# heart.net
KiCad netlist of a schematic drawn in EAGLE
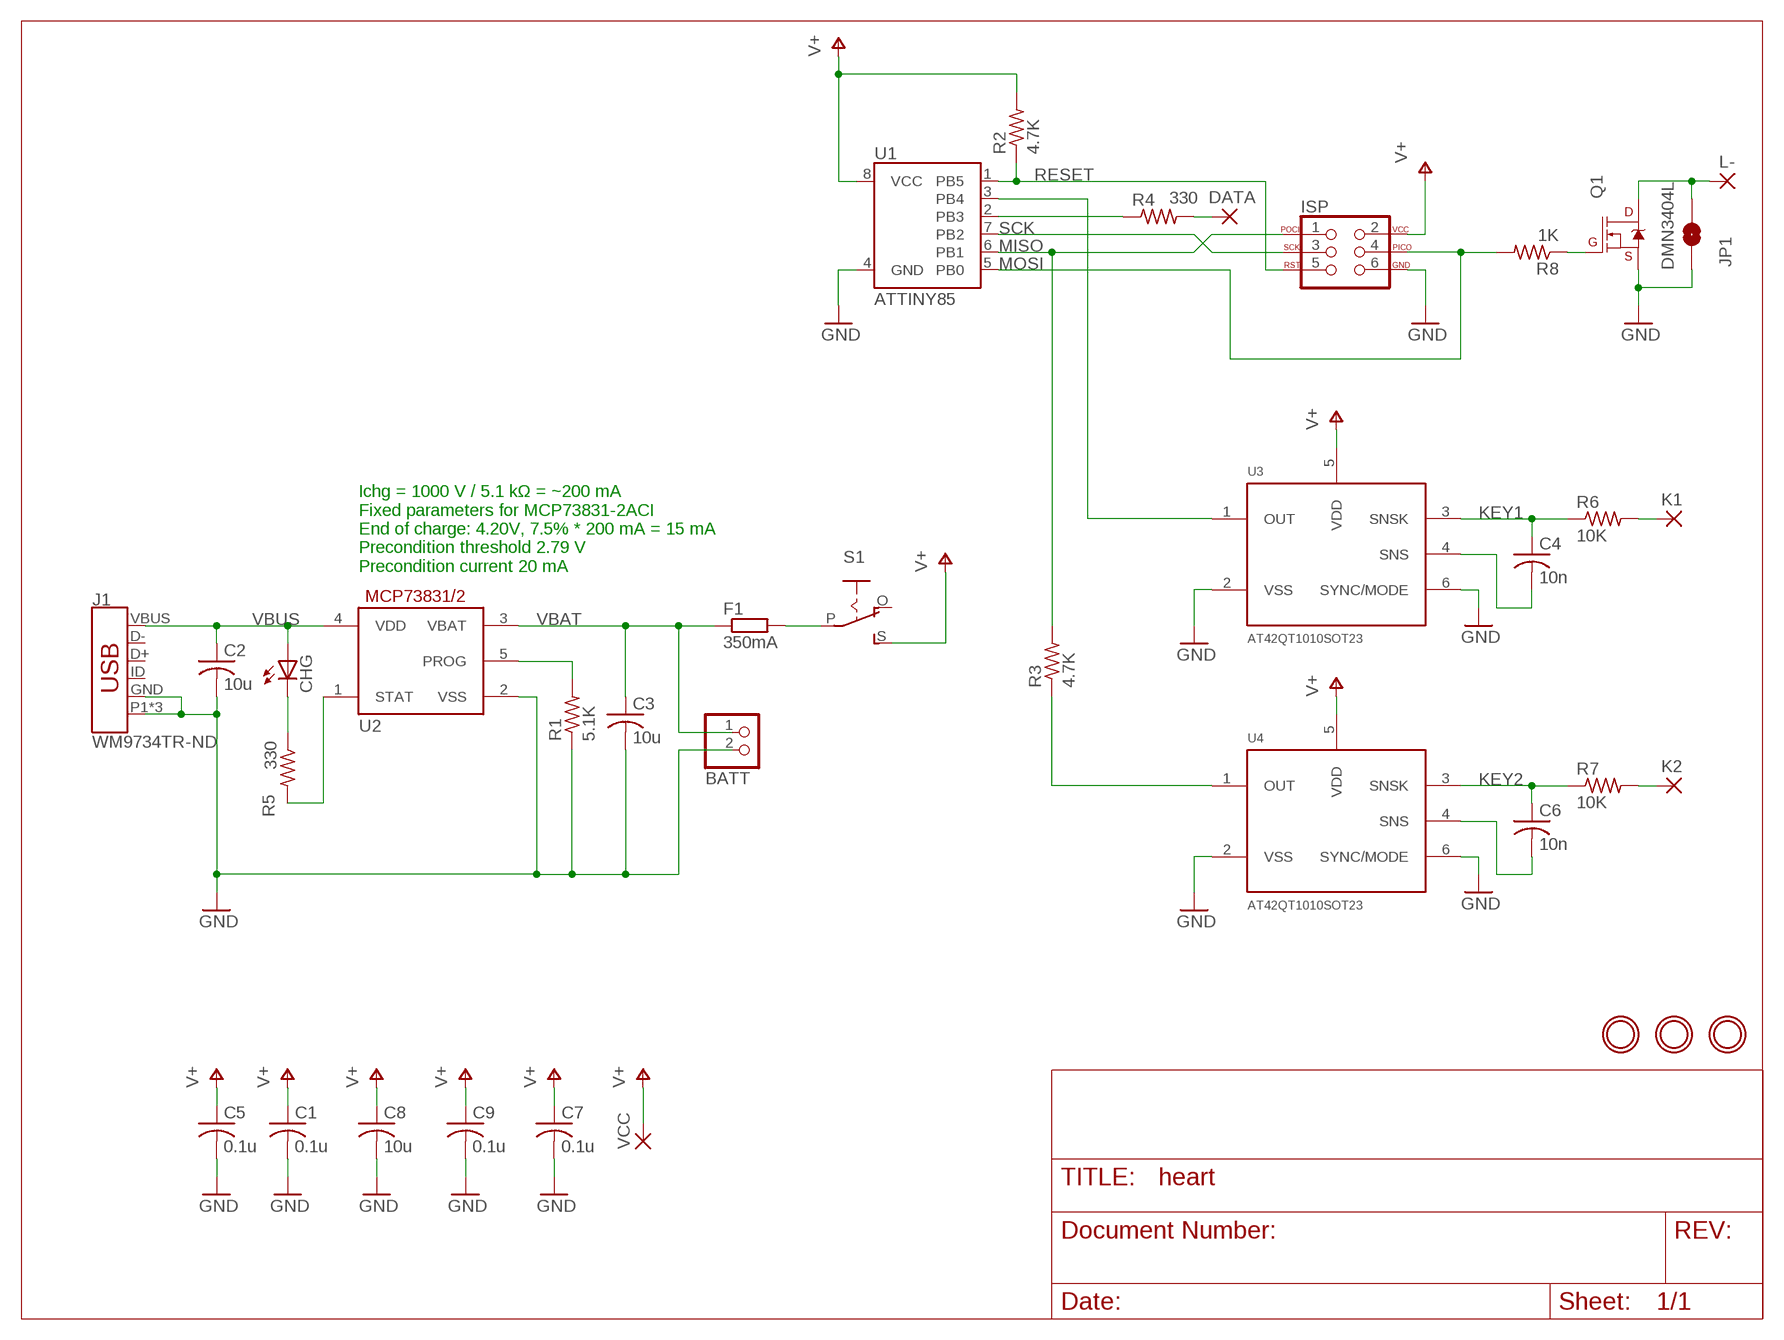
[diagram p0: schematic, sheet 1]

(export (version "E")
  (design (tool "Eeschema 10.0.6"))
  (components
    (comp (ref "BATT")
      (value "JST_2PIN-THM-RA")
      (footprint "eagle-import:JST-PH-2-THM-RA")
      (libsource (lib "eagle-import") (part "JST_2PIN-THM-RA"))
    )
    (comp (ref "C1")
      (value "0.1u")
      (footprint "eagle-import:C0603")
      (libsource (lib "eagle-import") (part "C-USC0603"))
    )
    (comp (ref "C2")
      (value "10u")
      (footprint "eagle-import:C0603")
      (libsource (lib "eagle-import") (part "C-USC0603"))
    )
    (comp (ref "C3")
      (value "10u")
      (footprint "eagle-import:C0603")
      (libsource (lib "eagle-import") (part "C-USC0603"))
    )
    (comp (ref "C4")
      (value "10n")
      (footprint "eagle-import:C0603")
      (libsource (lib "eagle-import") (part "C-USC0603"))
    )
    (comp (ref "C5")
      (value "0.1u")
      (footprint "eagle-import:C0603")
      (libsource (lib "eagle-import") (part "C-USC0603"))
    )
    (comp (ref "C6")
      (value "10n")
      (footprint "eagle-import:C0603")
      (libsource (lib "eagle-import") (part "C-USC0603"))
    )
    (comp (ref "C7")
      (value "0.1u")
      (footprint "eagle-import:C0603")
      (libsource (lib "eagle-import") (part "C-USC0603"))
    )
    (comp (ref "C8")
      (value "10u")
      (footprint "eagle-import:C0603")
      (libsource (lib "eagle-import") (part "C-USC0603"))
    )
    (comp (ref "C9")
      (value "0.1u")
      (footprint "eagle-import:C0603")
      (libsource (lib "eagle-import") (part "C-USC0603"))
    )
    (comp (ref "CHG")
      (value "LEDCHIP-LED0805")
      (footprint "eagle-import:CHIP-LED0805")
      (libsource (lib "eagle-import") (part "LEDCHIP-LED0805"))
    )
    (comp (ref "DATA")
      (value "2,15/1,0")
      (footprint "eagle-import:2,15_1,0")
      (libsource (lib "eagle-import") (part "2,15/1,0"))
    )
    (comp (ref "F1")
      (value "350mA")
      (footprint "eagle-import:R0603")
      (libsource (lib "eagle-import") (part "R-EU_R0603"))
    )
    (comp (ref "ISP")
      (value "AVR_SPI_PROG_3X2PTH")
      (footprint "eagle-import:2X3")
      (libsource (lib "eagle-import") (part "AVR_SPI_PROG_3X2PTH"))
    )
    (comp (ref "J1")
      (value "WM9734TR-ND")
      (footprint "eagle-import:USB-B-MICRO-SMD_VERT")
      (libsource (lib "eagle-import") (part "USB_MICRO-B_FEMALE-SMT-VERT"))
    )
    (comp (ref "JP1")
      (value "JUMPER-SMT_2_NO_NO-SILK")
      (footprint "eagle-import:SMT-JUMPER_2_NO_NO-SILK")
      (libsource (lib "eagle-import") (part "JUMPER-SMT_2_NO_NO-SILK"))
    )
    (comp (ref "K1")
      (value "2,15/1,0")
      (footprint "eagle-import:2,15_1,0")
      (libsource (lib "eagle-import") (part "2,15/1,0"))
    )
    (comp (ref "K2")
      (value "2,15/1,0")
      (footprint "eagle-import:2,15_1,0")
      (libsource (lib "eagle-import") (part "2,15/1,0"))
    )
    (comp (ref "L-")
      (value "2,15/1,0")
      (footprint "eagle-import:2,15_1,0")
      (libsource (lib "eagle-import") (part "2,15/1,0"))
    )
    (comp (ref "Q1")
      (value "DMN3404L")
      (footprint "eagle-import:SOT23-3")
      (libsource (lib "eagle-import") (part "MOSFET-NCH-AO3404A"))
    )
    (comp (ref "R1")
      (value "5.1K")
      (footprint "eagle-import:R0603")
      (libsource (lib "eagle-import") (part "R-US_R0603"))
    )
    (comp (ref "R2")
      (value "4.7K")
      (footprint "eagle-import:R0603")
      (libsource (lib "eagle-import") (part "R-US_R0603"))
    )
    (comp (ref "R3")
      (value "4.7K")
      (footprint "eagle-import:R0603")
      (libsource (lib "eagle-import") (part "R-US_R0603"))
    )
    (comp (ref "R4")
      (value "330")
      (footprint "eagle-import:R0603")
      (libsource (lib "eagle-import") (part "R-US_R0603"))
    )
    (comp (ref "R5")
      (value "330")
      (footprint "eagle-import:R0603")
      (libsource (lib "eagle-import") (part "R-US_R0603"))
    )
    (comp (ref "R6")
      (value "10K")
      (footprint "eagle-import:R0603")
      (libsource (lib "eagle-import") (part "R-US_R0603"))
    )
    (comp (ref "R7")
      (value "10K")
      (footprint "eagle-import:R0603")
      (libsource (lib "eagle-import") (part "R-US_R0603"))
    )
    (comp (ref "R8")
      (value "1K")
      (footprint "eagle-import:R0603")
      (libsource (lib "eagle-import") (part "R-US_R0603"))
    )
    (comp (ref "S1")
      (value "EG1218S")
      (footprint "eagle-import:EG1218")
      (libsource (lib "eagle-import") (part "EG1218S"))
    )
    (comp (ref "U$1")
      (value "MICROBUILDER_MOUNTINGHOLE2.0")
      (footprint "eagle-import:MICROBUILDER_MOUNTINGHOLE_2.0_PLATED")
      (libsource (lib "eagle-import") (part "MICROBUILDER_MOUNTINGHOLE2.0"))
    )
    (comp (ref "U$2")
      (value "MICROBUILDER_MOUNTINGHOLE2.0")
      (footprint "eagle-import:MICROBUILDER_MOUNTINGHOLE_2.0_PLATED")
      (libsource (lib "eagle-import") (part "MICROBUILDER_MOUNTINGHOLE2.0"))
    )
    (comp (ref "U$4")
      (value "MICROBUILDER_MOUNTINGHOLE2.0")
      (footprint "eagle-import:MICROBUILDER_MOUNTINGHOLE_2.0_PLATED")
      (libsource (lib "eagle-import") (part "MICROBUILDER_MOUNTINGHOLE2.0"))
    )
    (comp (ref "U1")
      (value "ATTINY85")
      (footprint "eagle-import:ATTINY85")
      (libsource (lib "eagle-import") (part "ATTINY85"))
    )
    (comp (ref "U2")
      (value "MCP73831/OT")
      (footprint "eagle-import:SOT23-5L")
      (libsource (lib "eagle-import") (part "MCP73831/OT"))
    )
    (comp (ref "U3")
      (value "AT42QT1010SOT23")
      (footprint "eagle-import:SOT23-6")
      (libsource (lib "eagle-import") (part "AT42QT1010SOT23"))
    )
    (comp (ref "U4")
      (value "AT42QT1010SOT23")
      (footprint "eagle-import:SOT23-6")
      (libsource (lib "eagle-import") (part "AT42QT1010SOT23"))
    )
    (comp (ref "VCC")
      (value "1,6/0,9")
      (footprint "eagle-import:1,6_0,9")
      (libsource (lib "eagle-import") (part "1,6/0,9"))
    )
  )
  (nets
    (net (code "1") (name "/KEY1") (class "Default")
      (node (ref "C4") (pin "1") (pinfunction "1_1") (pintype "passive"))
      (node (ref "R6") (pin "1") (pinfunction "1_1") (pintype "passive"))
      (node (ref "U3") (pin "3") (pinfunction "SNSK_3") (pintype "bidirectional"))
    )
    (net (code "2") (name "/KEY2") (class "Default")
      (node (ref "C6") (pin "1") (pinfunction "1_1") (pintype "passive"))
      (node (ref "R7") (pin "1") (pinfunction "1_1") (pintype "passive"))
      (node (ref "U4") (pin "3") (pinfunction "SNSK_3") (pintype "bidirectional"))
    )
    (net (code "3") (name "/MISO") (class "Default")
      (node (ref "ISP") (pin "1") (pinfunction "1_1") (pintype "passive"))
      (node (ref "R3") (pin "2") (pinfunction "2_2") (pintype "passive"))
      (node (ref "U1") (pin "6") (pinfunction "PB1_6") (pintype "bidirectional"))
    )
    (net (code "4") (name "/MOSI") (class "Default")
      (node (ref "ISP") (pin "4") (pinfunction "4_4") (pintype "passive"))
      (node (ref "R8") (pin "2") (pinfunction "2_2") (pintype "passive"))
      (node (ref "U1") (pin "5") (pinfunction "PB0_5") (pintype "bidirectional"))
    )
    (net (code "5") (name "/RESET") (class "Default")
      (node (ref "ISP") (pin "5") (pinfunction "5_5") (pintype "passive"))
      (node (ref "R2") (pin "1") (pinfunction "1_1") (pintype "passive"))
      (node (ref "U1") (pin "1") (pinfunction "PB5_1") (pintype "bidirectional"))
    )
    (net (code "6") (name "/SCK") (class "Default")
      (node (ref "ISP") (pin "3") (pinfunction "3_3") (pintype "passive"))
      (node (ref "U1") (pin "7") (pinfunction "PB2_7") (pintype "bidirectional"))
    )
    (net (code "7") (name "/VBAT") (class "Default")
      (node (ref "BATT") (pin "1") (pinfunction "2_1") (pintype "passive"))
      (node (ref "C3") (pin "1") (pinfunction "1_1") (pintype "passive"))
      (node (ref "F1") (pin "1") (pinfunction "1_1") (pintype "passive"))
      (node (ref "U2") (pin "3") (pinfunction "VBAT_3") (pintype "bidirectional"))
    )
    (net (code "8") (name "/VBUS") (class "Default")
      (node (ref "C2") (pin "1") (pinfunction "1_1") (pintype "passive"))
      (node (ref "CHG") (pin "A") (pinfunction "A_A") (pintype "passive"))
      (node (ref "J1") (pin "VBUS") (pinfunction "VBUS_VBUS") (pintype "power_in"))
      (node (ref "U2") (pin "4") (pinfunction "VDD_4") (pintype "power_in"))
    )
    (net (code "9") (name "GND") (class "Default")
      (node (ref "BATT") (pin "2") (pinfunction "1_2") (pintype "passive"))
      (node (ref "C1") (pin "2") (pinfunction "2_2") (pintype "passive"))
      (node (ref "C2") (pin "2") (pinfunction "2_2") (pintype "passive"))
      (node (ref "C3") (pin "2") (pinfunction "2_2") (pintype "passive"))
      (node (ref "C5") (pin "2") (pinfunction "2_2") (pintype "passive"))
      (node (ref "C7") (pin "2") (pinfunction "2_2") (pintype "passive"))
      (node (ref "C8") (pin "2") (pinfunction "2_2") (pintype "passive"))
      (node (ref "C9") (pin "2") (pinfunction "2_2") (pintype "passive"))
      (node (ref "ISP") (pin "6") (pinfunction "6_6") (pintype "passive"))
      (node (ref "J1") (pin "GND") (pinfunction "GND_GND") (pintype "power_in"))
      (node (ref "J1") (pin "P1") (pinfunction "SHIELD_P1") (pintype "bidirectional"))
      (node (ref "J1") (pin "P2") (pinfunction "SHIELD_P2") (pintype "bidirectional"))
      (node (ref "J1") (pin "P3") (pinfunction "SHIELD_P3") (pintype "bidirectional"))
      (node (ref "JP1") (pin "1") (pinfunction "1_1") (pintype "passive"))
      (node (ref "Q1") (pin "2") (pinfunction "S_2") (pintype "bidirectional"))
      (node (ref "R1") (pin "1") (pinfunction "1_1") (pintype "passive"))
      (node (ref "U1") (pin "4") (pinfunction "GND_4") (pintype "bidirectional"))
      (node (ref "U2") (pin "2") (pinfunction "VSS_2") (pintype "power_in"))
      (node (ref "U3") (pin "2") (pinfunction "VSS_2") (pintype "bidirectional"))
      (node (ref "U3") (pin "6") (pinfunction "SYNC/MODE_6") (pintype "bidirectional"))
      (node (ref "U4") (pin "2") (pinfunction "VSS_2") (pintype "bidirectional"))
      (node (ref "U4") (pin "6") (pinfunction "SYNC/MODE_6") (pintype "bidirectional"))
    )
    (net (code "10") (name "Net-(CHG-PadC)") (class "Default")
      (node (ref "CHG") (pin "C") (pinfunction "C_C") (pintype "passive"))
      (node (ref "R5") (pin "1") (pinfunction "1_1") (pintype "passive"))
    )
    (net (code "11") (name "Net-(DATA-P)") (class "Default")
      (node (ref "DATA") (pin "1") (pinfunction "P_1") (pintype "passive"))
      (node (ref "R4") (pin "2") (pinfunction "2_2") (pintype "passive"))
    )
    (net (code "12") (name "Net-(F1-Pad2)") (class "Default")
      (node (ref "F1") (pin "2") (pinfunction "2_2") (pintype "passive"))
      (node (ref "S1") (pin "P") (pinfunction "P_P") (pintype "passive"))
    )
    (net (code "13") (name "Net-(K1-P)") (class "Default")
      (node (ref "K1") (pin "1") (pinfunction "P_1") (pintype "passive"))
      (node (ref "R6") (pin "2") (pinfunction "2_2") (pintype "passive"))
    )
    (net (code "14") (name "Net-(K2-P)") (class "Default")
      (node (ref "K2") (pin "1") (pinfunction "P_1") (pintype "passive"))
      (node (ref "R7") (pin "2") (pinfunction "2_2") (pintype "passive"))
    )
    (net (code "15") (name "Net-(L--P)") (class "Default")
      (node (ref "JP1") (pin "2") (pinfunction "2_2") (pintype "passive"))
      (node (ref "L-") (pin "1") (pinfunction "P_1") (pintype "passive"))
      (node (ref "Q1") (pin "3") (pinfunction "D_3") (pintype "bidirectional"))
    )
    (net (code "16") (name "Net-(Q1-G)") (class "Default")
      (node (ref "Q1") (pin "1") (pinfunction "G_1") (pintype "bidirectional"))
      (node (ref "R8") (pin "1") (pinfunction "1_1") (pintype "passive"))
    )
    (net (code "17") (name "Net-(U1-PB3)") (class "Default")
      (node (ref "R4") (pin "1") (pinfunction "1_1") (pintype "passive"))
      (node (ref "U1") (pin "2") (pinfunction "PB3_2") (pintype "bidirectional"))
    )
    (net (code "18") (name "Net-(U1-PB4)") (class "Default")
      (node (ref "U1") (pin "3") (pinfunction "PB4_3") (pintype "bidirectional"))
      (node (ref "U3") (pin "1") (pinfunction "OUT_1") (pintype "bidirectional"))
    )
    (net (code "19") (name "Net-(U2-PROG)") (class "Default")
      (node (ref "R1") (pin "2") (pinfunction "2_2") (pintype "passive"))
      (node (ref "U2") (pin "5") (pinfunction "PROG_5") (pintype "input"))
    )
    (net (code "20") (name "Net-(U2-STAT)") (class "Default")
      (node (ref "R5") (pin "2") (pinfunction "2_2") (pintype "passive"))
      (node (ref "U2") (pin "1") (pinfunction "STAT_1") (pintype "output"))
    )
    (net (code "21") (name "Net-(U3-SNS)") (class "Default")
      (node (ref "C4") (pin "2") (pinfunction "2_2") (pintype "passive"))
      (node (ref "U3") (pin "4") (pinfunction "SNS_4") (pintype "bidirectional"))
    )
    (net (code "22") (name "Net-(U4-OUT)") (class "Default")
      (node (ref "R3") (pin "1") (pinfunction "1_1") (pintype "passive"))
      (node (ref "U4") (pin "1") (pinfunction "OUT_1") (pintype "bidirectional"))
    )
    (net (code "23") (name "Net-(U4-SNS)") (class "Default")
      (node (ref "C6") (pin "2") (pinfunction "2_2") (pintype "passive"))
      (node (ref "U4") (pin "4") (pinfunction "SNS_4") (pintype "bidirectional"))
    )
    (net (code "24") (name "V+") (class "Default")
      (node (ref "C1") (pin "1") (pinfunction "1_1") (pintype "passive"))
      (node (ref "C5") (pin "1") (pinfunction "1_1") (pintype "passive"))
      (node (ref "C7") (pin "1") (pinfunction "1_1") (pintype "passive"))
      (node (ref "C8") (pin "1") (pinfunction "1_1") (pintype "passive"))
      (node (ref "C9") (pin "1") (pinfunction "1_1") (pintype "passive"))
      (node (ref "ISP") (pin "2") (pinfunction "2_2") (pintype "passive"))
      (node (ref "R2") (pin "2") (pinfunction "2_2") (pintype "passive"))
      (node (ref "S1") (pin "S") (pinfunction "S_S") (pintype "passive"))
      (node (ref "U1") (pin "8") (pinfunction "VCC_8") (pintype "bidirectional"))
      (node (ref "U3") (pin "5") (pinfunction "VDD_5") (pintype "bidirectional"))
      (node (ref "U4") (pin "5") (pinfunction "VDD_5") (pintype "bidirectional"))
      (node (ref "VCC") (pin "1") (pinfunction "P_1") (pintype "passive"))
    )
    (net (code "25") (name "unconnected-(J1-PadD+)") (class "Default")
      (node (ref "J1") (pin "D+") (pinfunction "D+_D+") (pintype "bidirectional"))
    )
    (net (code "26") (name "unconnected-(J1-PadD-)") (class "Default")
      (node (ref "J1") (pin "D-") (pinfunction "D-_D-") (pintype "bidirectional"))
    )
    (net (code "27") (name "unconnected-(J1-PadID)") (class "Default")
      (node (ref "J1") (pin "ID") (pinfunction "ID_ID") (pintype "bidirectional"))
    )
    (net (code "28") (name "unconnected-(S1-PadO)") (class "Default")
      (node (ref "S1") (pin "O") (pinfunction "O_O") (pintype "passive"))
    )
  )
)
